# ESP12_Breakout.net
KiCad netlist of a schematic drawn in EAGLE
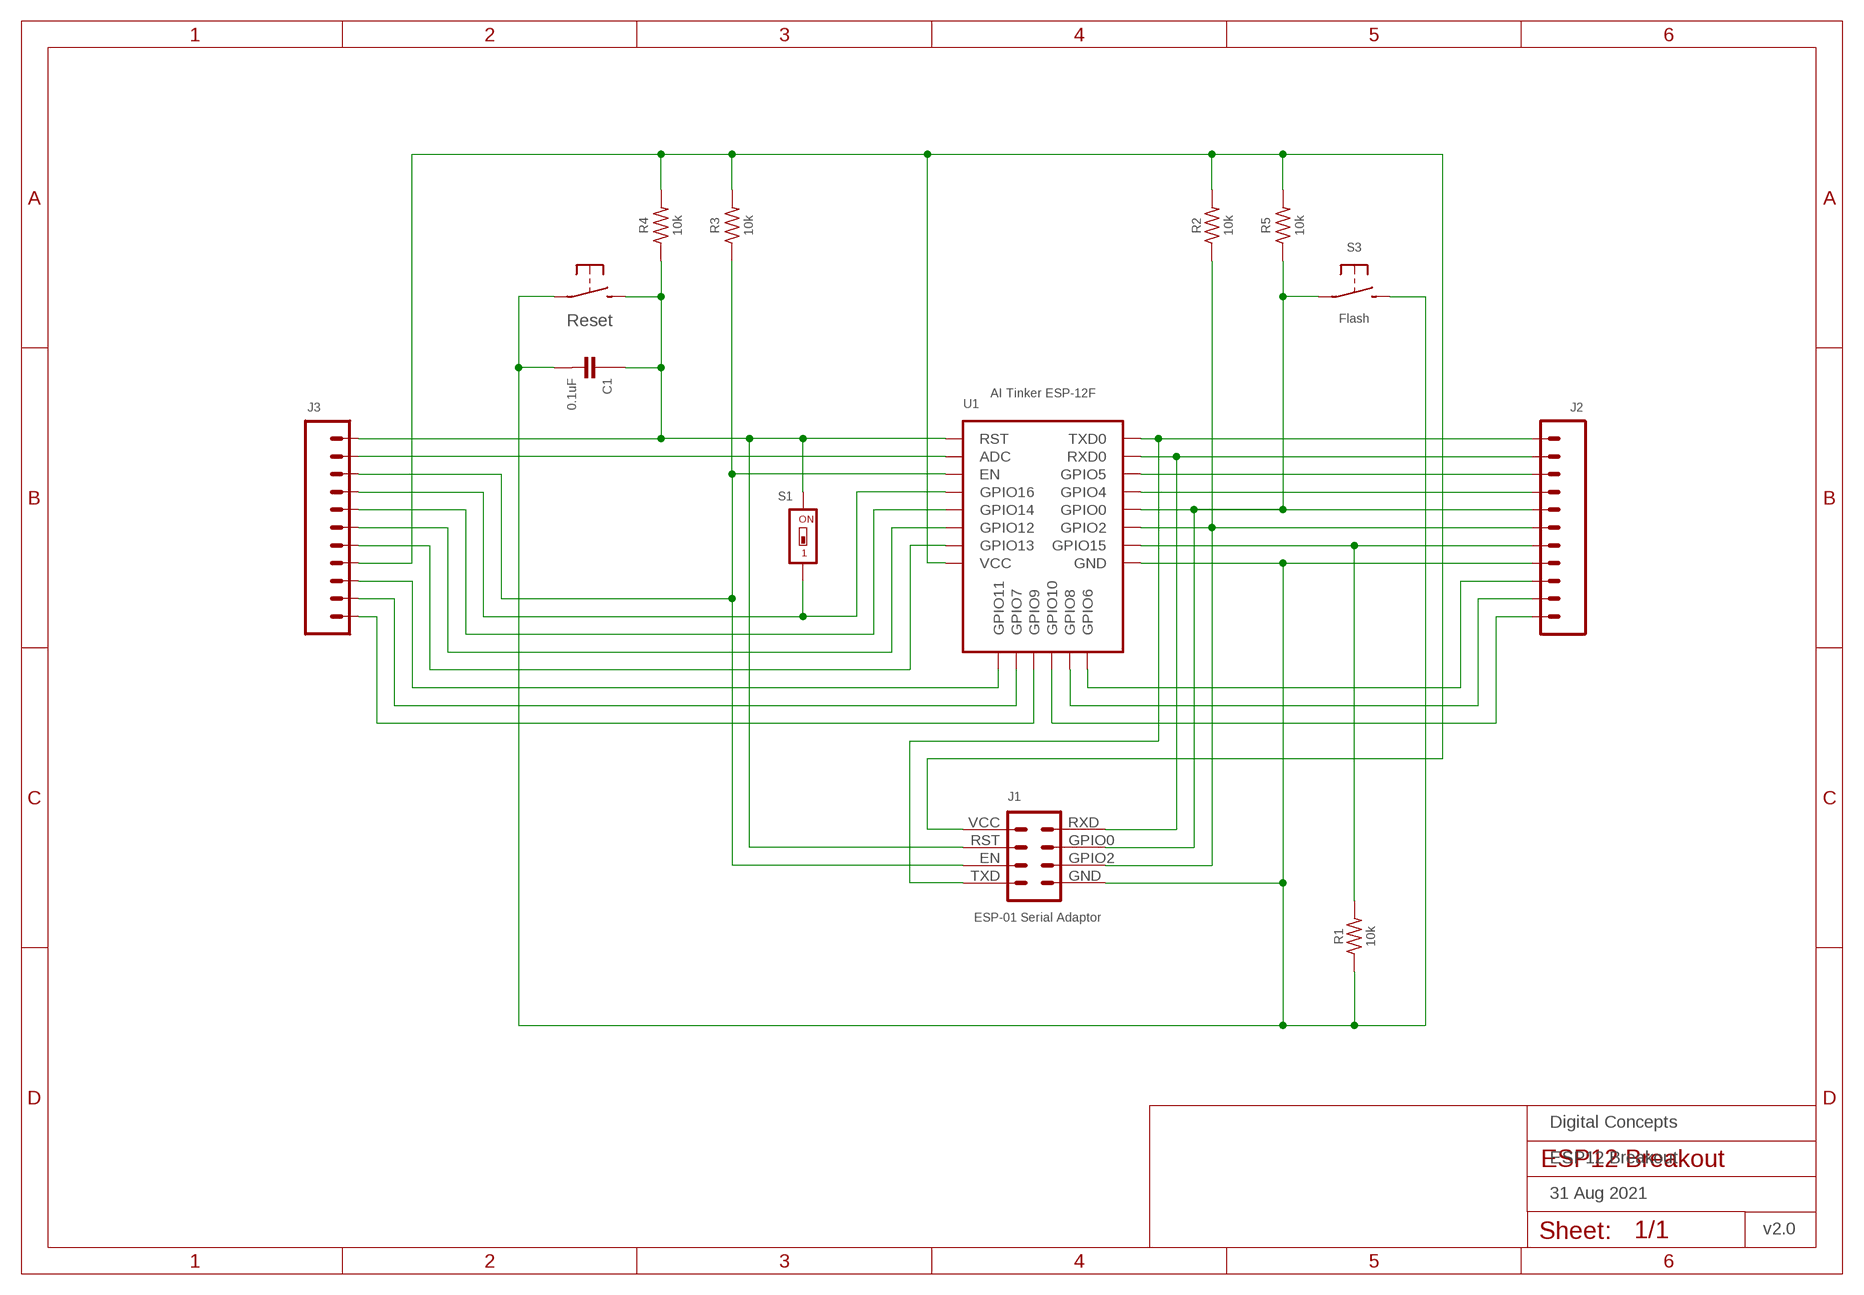
[diagram p0: schematic, sheet 1]

(export (version "E")
  (design (tool "Eeschema 10.0.6"))
  (components
    (comp (ref "C1")
      (value "0.1uF")
      (footprint "eagle-import:C0805")
      (libsource (lib "eagle-import") (part "CAPACITOR-0805"))
    )
    (comp (ref "J1")
      (value "ESP-01 Serial Adaptor")
      (footprint "eagle-import:CONN_2X4-ESP-01-SERIAL")
      (libsource (lib "eagle-import") (part "ESP-01-SERIAL-ADAPTOR"))
    )
    (comp (ref "J2")
      (value "HEADER-1X11-GENERIC")
      (footprint "eagle-import:CONN_11-GENERIC")
      (libsource (lib "eagle-import") (part "HEADER-1X11-GENERIC"))
    )
    (comp (ref "J3")
      (value "HEADER-1X11-GENERIC")
      (footprint "eagle-import:CONN_11-GENERIC")
      (libsource (lib "eagle-import") (part "HEADER-1X11-GENERIC"))
    )
    (comp (ref "R1")
      (value "10k")
      (footprint "eagle-import:R0805")
      (libsource (lib "eagle-import") (part "RESISTORR0805"))
    )
    (comp (ref "R2")
      (value "10k")
      (footprint "eagle-import:R0805")
      (libsource (lib "eagle-import") (part "RESISTORR0805"))
    )
    (comp (ref "R3")
      (value "10k")
      (footprint "eagle-import:R0805")
      (libsource (lib "eagle-import") (part "RESISTORR0805"))
    )
    (comp (ref "R4")
      (value "10k")
      (footprint "eagle-import:R0805")
      (libsource (lib "eagle-import") (part "RESISTORR0805"))
    )
    (comp (ref "R5")
      (value "10k")
      (footprint "eagle-import:R0805")
      (libsource (lib "eagle-import") (part "RESISTORR0805"))
    )
    (comp (ref "S1")
      (value "Wake")
      (footprint "eagle-import:SMD-001")
      (libsource (lib "eagle-import") (part "SWITCH-DIP-SWS001"))
    )
    (comp (ref "S2")
      (value "Reset")
      (footprint "eagle-import:SWITCH-2-PAD")
      (libsource (lib "eagle-import") (part "SWITCH-MOMENTARY-2-PIN"))
    )
    (comp (ref "S3")
      (value "Flash")
      (footprint "eagle-import:SWITCH-2-PAD")
      (libsource (lib "eagle-import") (part "SWITCH-MOMENTARY-2-PIN"))
    )
    (comp (ref "U1")
      (value "AI Tinker ESP-12F")
      (footprint "eagle-import:ESP-12E_F")
      (libsource (lib "eagle-import") (part "ESP-12E/F"))
    )
  )
  (nets
    (net (code "1") (name "Net-(J1-1)") (class "Default")
      (node (ref "C1") (pin "2") (pinfunction "2_2") (pintype "passive"))
      (node (ref "J1") (pin "GND") (pinfunction "1_GND") (pintype "passive"))
      (node (ref "J2") (pin "4") (pinfunction "4_4") (pintype "passive"))
      (node (ref "R1") (pin "1") (pinfunction "1_1") (pintype "passive"))
      (node (ref "S2") (pin "P$1") (pinfunction "P_P$1") (pintype "passive"))
      (node (ref "S3") (pin "P$2") (pinfunction "S_P$2") (pintype "passive"))
      (node (ref "U1") (pin "GND") (pinfunction "GND_GND") (pintype "bidirectional"))
    )
    (net (code "2") (name "Net-(J1-2)") (class "Default")
      (node (ref "J1") (pin "GPIO2") (pinfunction "2_GPIO2") (pintype "passive"))
      (node (ref "J2") (pin "6") (pinfunction "6_6") (pintype "passive"))
      (node (ref "R2") (pin "1") (pinfunction "1_1") (pintype "passive"))
      (node (ref "U1") (pin "GPIO2") (pinfunction "GPIO2_GPIO2") (pintype "bidirectional"))
    )
    (net (code "3") (name "Net-(J1-3)") (class "Default")
      (node (ref "J1") (pin "GPIO0") (pinfunction "3_GPIO0") (pintype "passive"))
      (node (ref "J2") (pin "7") (pinfunction "7_7") (pintype "passive"))
      (node (ref "R5") (pin "1") (pinfunction "1_1") (pintype "passive"))
      (node (ref "S3") (pin "P$1") (pinfunction "P_P$1") (pintype "passive"))
      (node (ref "U1") (pin "GPIO0") (pinfunction "GPIO0_GPIO0") (pintype "bidirectional"))
    )
    (net (code "4") (name "Net-(J1-4)") (class "Default")
      (node (ref "J1") (pin "RXD") (pinfunction "4_RXD") (pintype "passive"))
      (node (ref "J2") (pin "10") (pinfunction "10_10") (pintype "passive"))
      (node (ref "U1") (pin "RXD0") (pinfunction "RXD0_RXD0") (pintype "bidirectional"))
    )
    (net (code "5") (name "Net-(J1-5)") (class "Default")
      (node (ref "J1") (pin "VCC") (pinfunction "5_VCC") (pintype "passive"))
      (node (ref "J3") (pin "4") (pinfunction "4_4") (pintype "passive"))
      (node (ref "R2") (pin "2") (pinfunction "2_2") (pintype "passive"))
      (node (ref "R3") (pin "2") (pinfunction "2_2") (pintype "passive"))
      (node (ref "R4") (pin "2") (pinfunction "2_2") (pintype "passive"))
      (node (ref "R5") (pin "2") (pinfunction "2_2") (pintype "passive"))
      (node (ref "U1") (pin "VCC") (pinfunction "VCC_VCC") (pintype "bidirectional"))
    )
    (net (code "6") (name "Net-(J1-6)") (class "Default")
      (node (ref "C1") (pin "1") (pinfunction "1_1") (pintype "passive"))
      (node (ref "J1") (pin "RST") (pinfunction "6_RST") (pintype "passive"))
      (node (ref "J3") (pin "11") (pinfunction "11_11") (pintype "passive"))
      (node (ref "R4") (pin "1") (pinfunction "1_1") (pintype "passive"))
      (node (ref "S1") (pin "2") (pinfunction "2_2") (pintype "passive"))
      (node (ref "S2") (pin "P$2") (pinfunction "S_P$2") (pintype "passive"))
      (node (ref "U1") (pin "RST") (pinfunction "RST_RST") (pintype "bidirectional"))
    )
    (net (code "7") (name "Net-(J1-7)") (class "Default")
      (node (ref "J1") (pin "EN") (pinfunction "7_EN") (pintype "passive"))
      (node (ref "J3") (pin "9") (pinfunction "9_9") (pintype "passive"))
      (node (ref "R3") (pin "1") (pinfunction "1_1") (pintype "passive"))
      (node (ref "U1") (pin "EN") (pinfunction "EN_EN") (pintype "bidirectional"))
    )
    (net (code "8") (name "Net-(J1-8)") (class "Default")
      (node (ref "J1") (pin "TXD") (pinfunction "8_TXD") (pintype "passive"))
      (node (ref "J2") (pin "11") (pinfunction "11_11") (pintype "passive"))
      (node (ref "U1") (pin "TXD0") (pinfunction "TXD0_TXD0") (pintype "bidirectional"))
    )
    (net (code "9") (name "Net-(J2-Pad1)") (class "Default")
      (node (ref "J2") (pin "1") (pinfunction "1_1") (pintype "passive"))
      (node (ref "U1") (pin "GPIO10") (pinfunction "GPIO10_GPIO10") (pintype "bidirectional"))
    )
    (net (code "10") (name "Net-(J2-Pad5)") (class "Default")
      (node (ref "J2") (pin "5") (pinfunction "5_5") (pintype "passive"))
      (node (ref "R1") (pin "2") (pinfunction "2_2") (pintype "passive"))
      (node (ref "U1") (pin "GPIO15") (pinfunction "GPIO15_GPIO15") (pintype "bidirectional"))
    )
    (net (code "11") (name "Net-(J2-Pad8)") (class "Default")
      (node (ref "J2") (pin "8") (pinfunction "8_8") (pintype "passive"))
      (node (ref "U1") (pin "GPIO4") (pinfunction "GPIO4_GPIO4") (pintype "bidirectional"))
    )
    (net (code "12") (name "Net-(J2-Pad9)") (class "Default")
      (node (ref "J2") (pin "9") (pinfunction "9_9") (pintype "passive"))
      (node (ref "U1") (pin "GPIO5") (pinfunction "GPIO5_GPIO5") (pintype "bidirectional"))
    )
    (net (code "13") (name "Net-(J3-Pad1)") (class "Default")
      (node (ref "J3") (pin "1") (pinfunction "1_1") (pintype "passive"))
      (node (ref "U1") (pin "GPIO9") (pinfunction "GPIO9_GPIO9") (pintype "bidirectional"))
    )
    (net (code "14") (name "Net-(J3-Pad5)") (class "Default")
      (node (ref "J3") (pin "5") (pinfunction "5_5") (pintype "passive"))
      (node (ref "U1") (pin "GPIO13") (pinfunction "GPIO13_GPIO13") (pintype "bidirectional"))
    )
    (net (code "15") (name "Net-(J3-Pad6)") (class "Default")
      (node (ref "J3") (pin "6") (pinfunction "6_6") (pintype "passive"))
      (node (ref "U1") (pin "GPIO12") (pinfunction "GPIO12_GPIO12") (pintype "bidirectional"))
    )
    (net (code "16") (name "Net-(J3-Pad7)") (class "Default")
      (node (ref "J3") (pin "7") (pinfunction "7_7") (pintype "passive"))
      (node (ref "U1") (pin "GPIO14") (pinfunction "GPIO14_GPIO14") (pintype "bidirectional"))
    )
    (net (code "17") (name "Net-(J3-Pad8)") (class "Default")
      (node (ref "J3") (pin "8") (pinfunction "8_8") (pintype "passive"))
      (node (ref "S1") (pin "1") (pinfunction "1_1") (pintype "passive"))
      (node (ref "U1") (pin "GPIO16") (pinfunction "GPIO16_GPIO16") (pintype "bidirectional"))
    )
    (net (code "18") (name "Net-(J3-Pad10)") (class "Default")
      (node (ref "J3") (pin "10") (pinfunction "10_10") (pintype "passive"))
      (node (ref "U1") (pin "ADC") (pinfunction "ADC_ADC") (pintype "bidirectional"))
    )
    (net (code "19") (name "Net-(U1-GPIO6)") (class "Default")
      (node (ref "J2") (pin "3") (pinfunction "3_3") (pintype "passive"))
      (node (ref "U1") (pin "SCLK") (pinfunction "GPIO6_SCLK") (pintype "bidirectional"))
    )
    (net (code "20") (name "Net-(U1-GPIO7)") (class "Default")
      (node (ref "J3") (pin "2") (pinfunction "2_2") (pintype "passive"))
      (node (ref "U1") (pin "MISO") (pinfunction "GPIO7_MISO") (pintype "bidirectional"))
    )
    (net (code "21") (name "Net-(U1-GPIO8)") (class "Default")
      (node (ref "J2") (pin "2") (pinfunction "2_2") (pintype "passive"))
      (node (ref "U1") (pin "MOSI") (pinfunction "GPIO8_MOSI") (pintype "bidirectional"))
    )
    (net (code "22") (name "Net-(U1-GPIO11)") (class "Default")
      (node (ref "J3") (pin "3") (pinfunction "3_3") (pintype "passive"))
      (node (ref "U1") (pin "CS0") (pinfunction "GPIO11_CS0") (pintype "bidirectional"))
    )
  )
)
